# Grabber_DIOT.net
KiCad netlist of a schematic drawn in Altium Designer
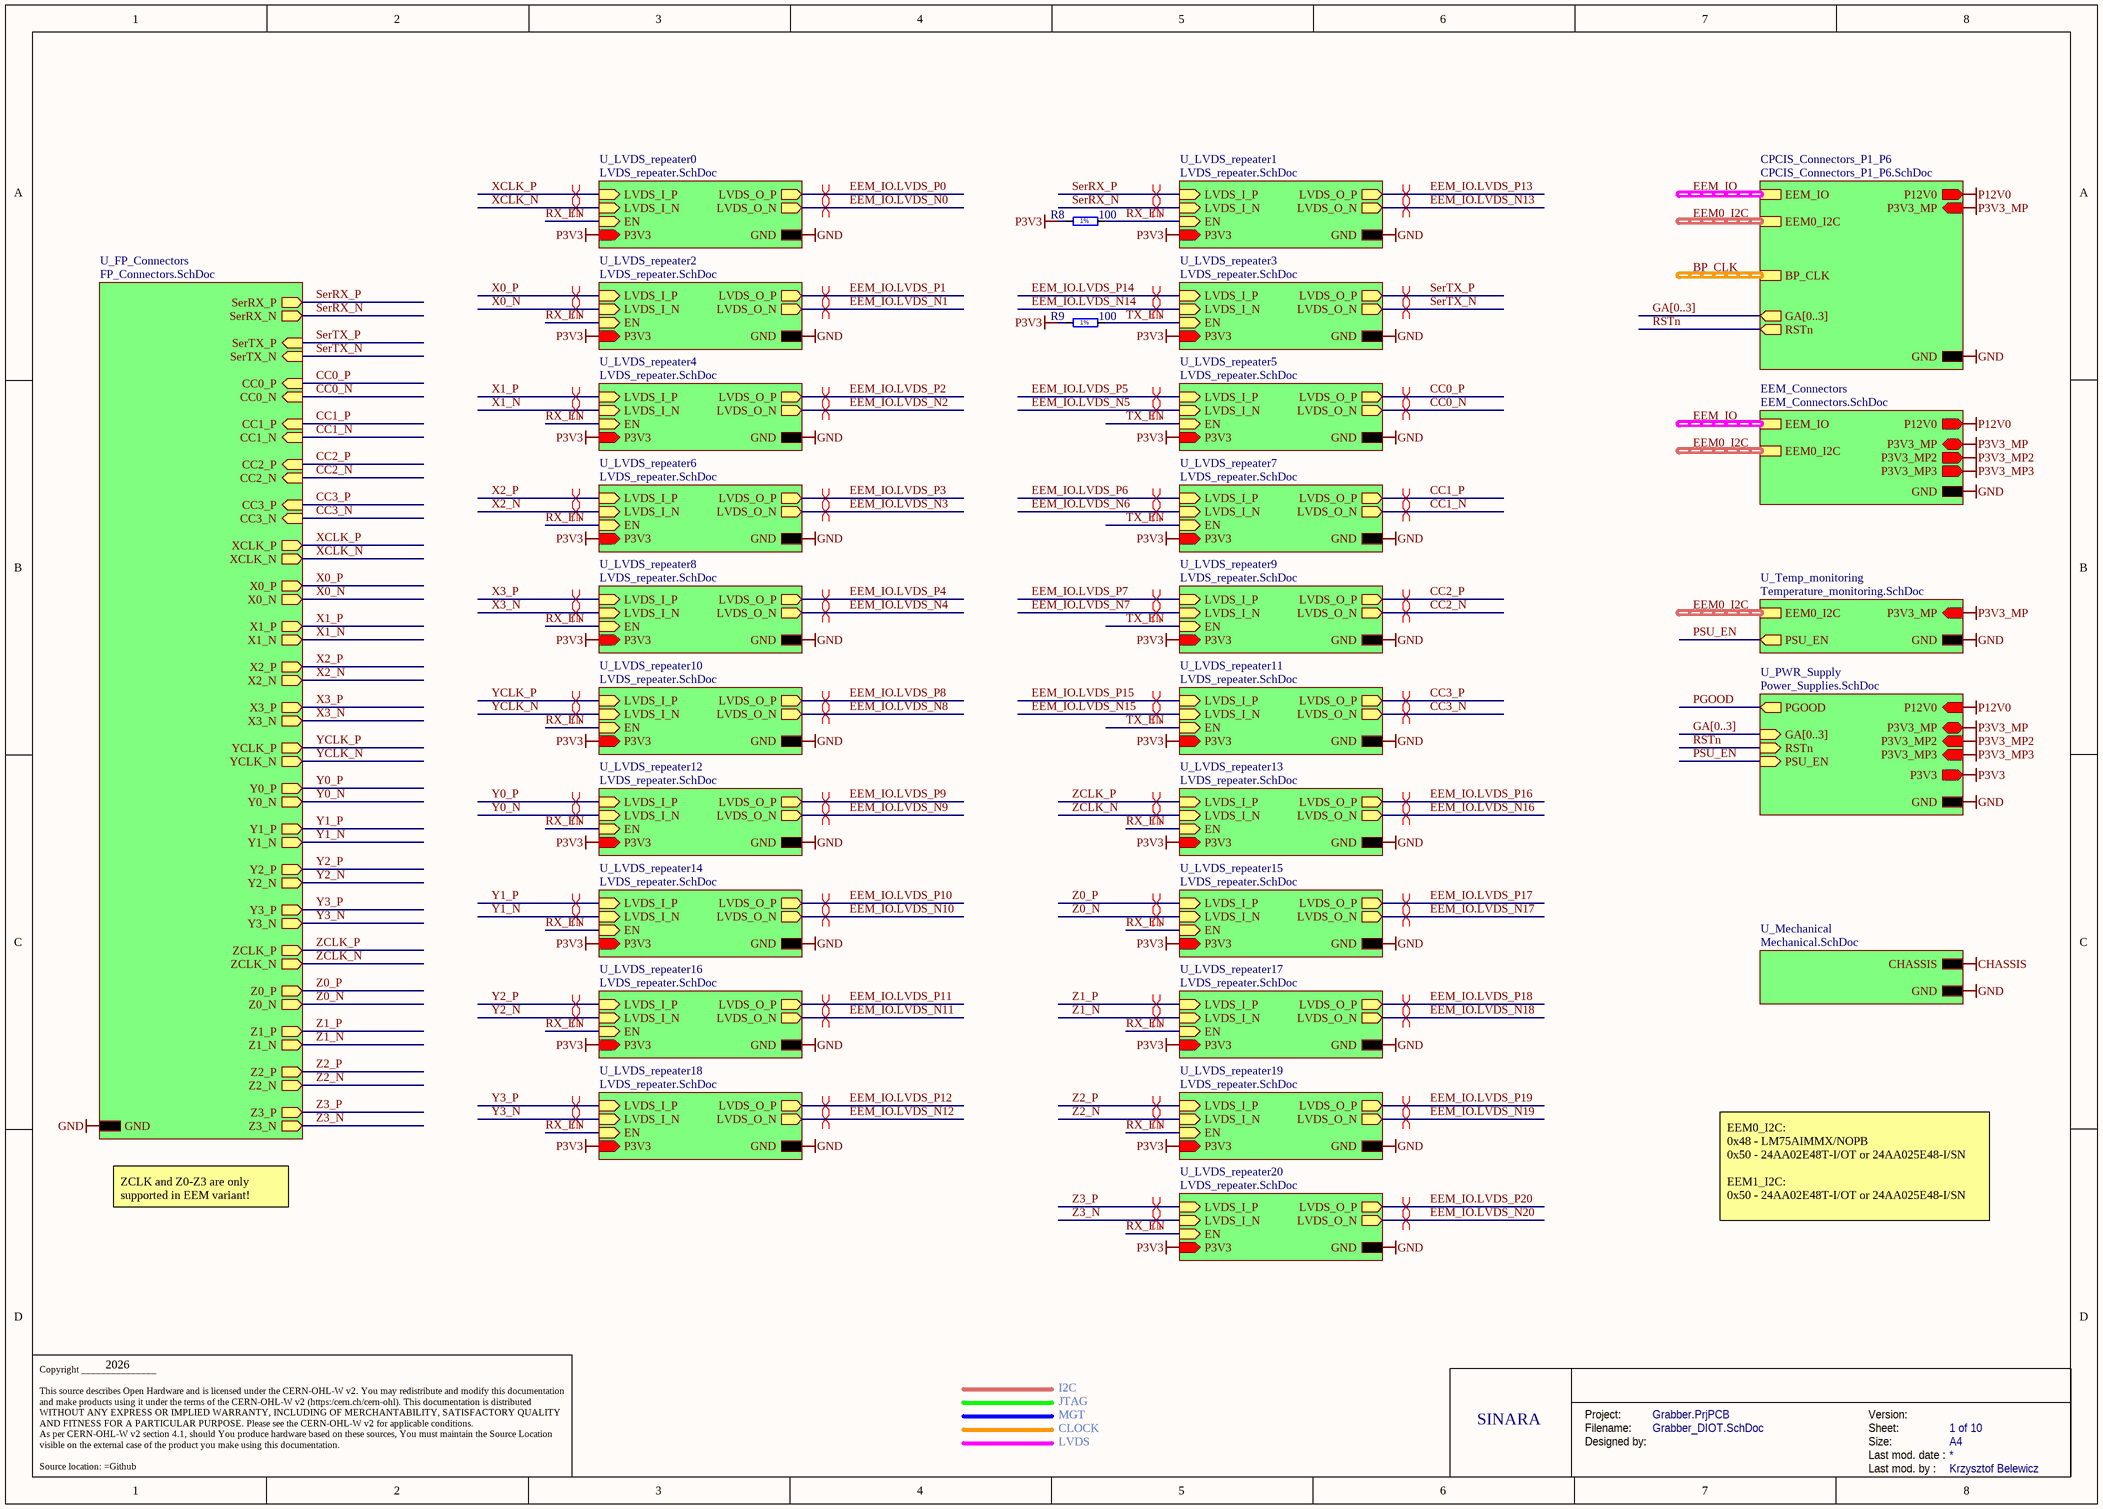
[diagram p0: Grabber_DIOT.SchDoc]

(export (version "E")
  (design (tool "Eeschema 10.0.6"))
  (components
    (comp (ref "R8")
      (value "100")
      (footprint "RESC1005X40N")
      (description "Resistor - 1%")
      (fields
        (field (name "PART NUMBER") "R0402_100R_1%_0.1W_100PPM")
        (field (name "POWER") "0.1W")
        (field (name "AUTHOR") "CERN DEM JLC")
      )
      (libsource (lib "Resistors") (part "Resistor - 1%"))
    )
    (comp (ref "R9")
      (value "100")
      (footprint "RESC1005X40N")
      (description "Resistor - 1%")
      (fields
        (field (name "PART NUMBER") "R0402_100R_1%_0.1W_100PPM")
        (field (name "POWER") "0.1W")
        (field (name "AUTHOR") "CERN DEM JLC")
      )
      (libsource (lib "Resistors") (part "Resistor - 1%"))
    )
  )
  (nets
    (net (code "62") (name "/RX_EN") (class "Default")
      (node (ref "R8") (pin "2") (pinfunction "2_2") (pintype "passive"))
    )
    (net (code "67") (name "/TX_EN") (class "Default")
      (node (ref "R9") (pin "2") (pinfunction "2_2") (pintype "passive"))
    )
    (net (code "103") (name "P3V3") (class "Default")
      (node (ref "R8") (pin "1") (pinfunction "1_1") (pintype "passive"))
      (node (ref "R9") (pin "1") (pinfunction "1_1") (pintype "passive"))
    )
  )
)
